# Sheet1.net
KiCad netlist of a schematic drawn in Altium Designer
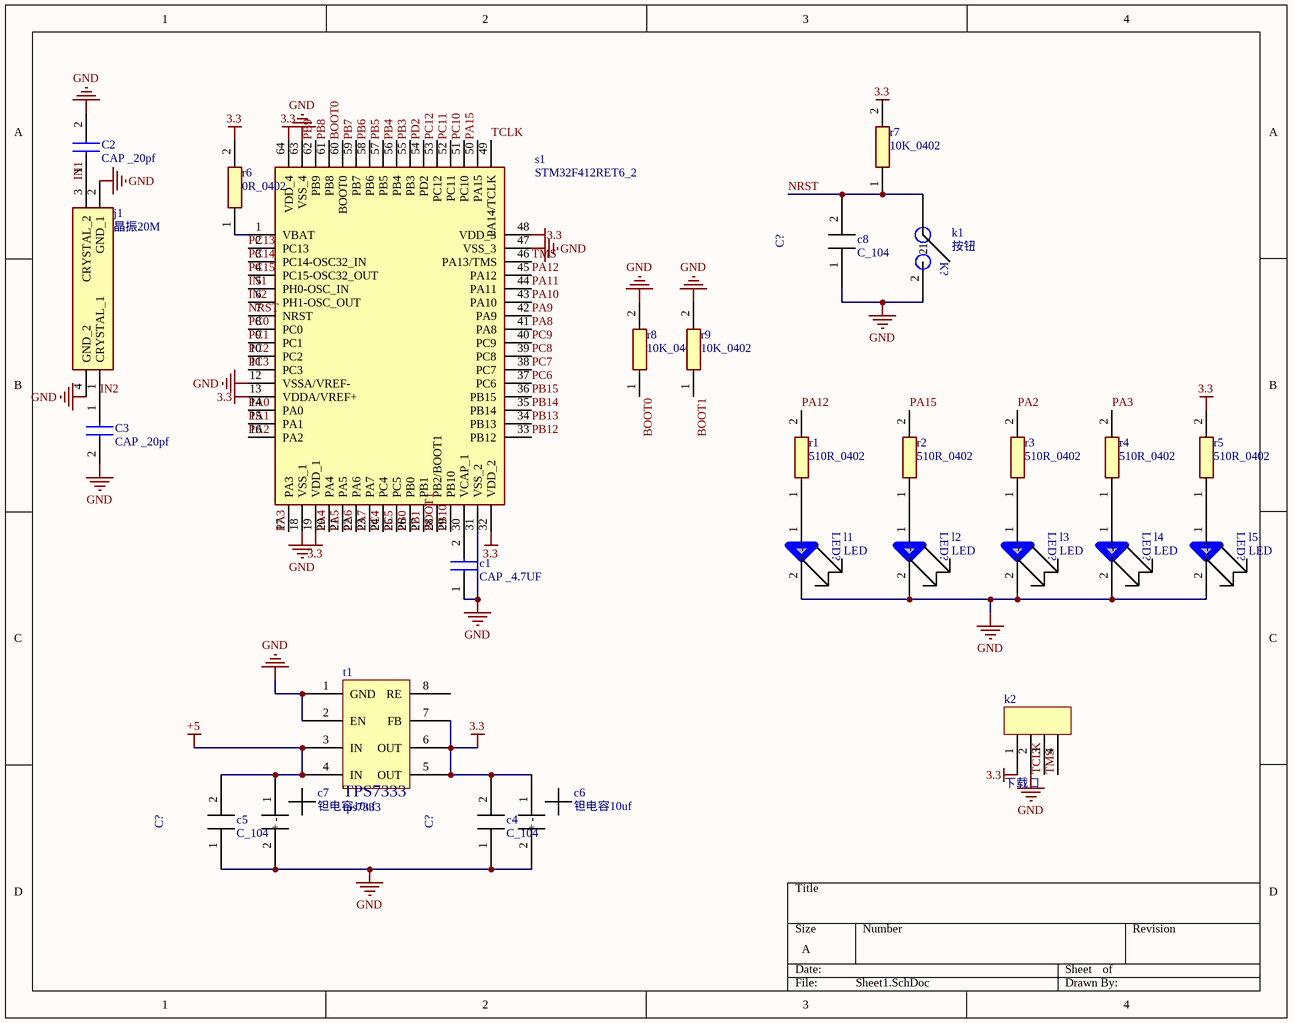
[diagram p0: Sheet1.SchDoc]

(export (version "E")
  (design (tool "Eeschema 10.0.6"))
  (components
    (comp (ref "c1")
      (value "CAP _4.7UF")
      (footprint "cap_0402")
      (libsource (lib "zengjie_Integrated_Library") (part "CAP _20pf"))
    )
    (comp (ref "C2")
      (value "CAP _20pf")
      (footprint "cap_0402")
      (libsource (lib "zengjie_Integrated_Library") (part "CAP _20pf"))
    )
    (comp (ref "C3")
      (value "CAP _20pf")
      (footprint "cap_0402")
      (libsource (lib "zengjie_Integrated_Library") (part "CAP _20pf"))
    )
    (comp (ref "c4")
      (value "C_104")
      (footprint "RC0603")
      (libsource (lib "zengjie_Integrated_Library") (part "C_104"))
    )
    (comp (ref "c5")
      (value "C_104")
      (footprint "RC0603")
      (libsource (lib "zengjie_Integrated_Library") (part "C_104"))
    )
    (comp (ref "c6")
      (value "钽电容10uf")
      (footprint "钽电容10uf 3216")
      (libsource (lib "zengjie_Integrated_Library") (part "钽电容10uf"))
    )
    (comp (ref "c7")
      (value "钽电容10uf")
      (footprint "钽电容10uf 3216")
      (libsource (lib "zengjie_Integrated_Library") (part "钽电容10uf"))
    )
    (comp (ref "c8")
      (value "C_104")
      (footprint "RC0603")
      (libsource (lib "zengjie_Integrated_Library") (part "C_104"))
    )
    (comp (ref "j1")
      (value "晶振20M")
      (footprint "晶振20M")
      (libsource (lib "zengjie_Integrated_Library") (part "晶振20M"))
    )
    (comp (ref "k1")
      (value "按钮")
      (footprint "SMT-KEY")
      (libsource (lib "zengjie_Integrated_Library") (part "按钮"))
    )
    (comp (ref "k2")
      (value "下载口")
      (footprint "贴片4位接口")
      (libsource (lib "zengjie_Integrated_Library") (part "贴片4位"))
    )
    (comp (ref "l1")
      (value "LED")
      (footprint "LED0805")
      (libsource (lib "zengjie_Integrated_Library") (part "LED"))
    )
    (comp (ref "l2")
      (value "LED")
      (footprint "LED0805")
      (libsource (lib "zengjie_Integrated_Library") (part "LED"))
    )
    (comp (ref "l3")
      (value "LED")
      (footprint "LED0805")
      (libsource (lib "zengjie_Integrated_Library") (part "LED"))
    )
    (comp (ref "l4")
      (value "LED")
      (footprint "LED0805")
      (libsource (lib "zengjie_Integrated_Library") (part "LED"))
    )
    (comp (ref "l5")
      (value "LED")
      (footprint "LED0805")
      (libsource (lib "zengjie_Integrated_Library") (part "LED"))
    )
    (comp (ref "r1")
      (value "510R_0402")
      (footprint "RC0402")
      (libsource (lib "zengjie_Integrated_Library") (part "510R_0402"))
    )
    (comp (ref "r2")
      (value "510R_0402")
      (footprint "RC0402")
      (libsource (lib "zengjie_Integrated_Library") (part "510R_0402"))
    )
    (comp (ref "r3")
      (value "510R_0402")
      (footprint "RC0402")
      (libsource (lib "zengjie_Integrated_Library") (part "510R_0402"))
    )
    (comp (ref "r4")
      (value "510R_0402")
      (footprint "RC0402")
      (libsource (lib "zengjie_Integrated_Library") (part "510R_0402"))
    )
    (comp (ref "r5")
      (value "510R_0402")
      (footprint "RC0402")
      (libsource (lib "zengjie_Integrated_Library") (part "510R_0402"))
    )
    (comp (ref "r6")
      (value "0R_0402")
      (footprint "RC0402")
      (libsource (lib "zengjie_Integrated_Library") (part "0R_0402"))
    )
    (comp (ref "r7")
      (value "10K_0402")
      (footprint "RC0402")
      (libsource (lib "zengjie_Integrated_Library") (part "10K_0402"))
    )
    (comp (ref "r8")
      (value "10K_0402")
      (footprint "RC0402")
      (libsource (lib "zengjie_Integrated_Library") (part "10K_0402"))
    )
    (comp (ref "r9")
      (value "10K_0402")
      (footprint "RC0402")
      (libsource (lib "zengjie_Integrated_Library") (part "10K_0402"))
    )
    (comp (ref "s1")
      (value "STM32F412RET6_2")
      (footprint "stm32f412ret6 _2")
      (libsource (lib "zengjie_Integrated_Library") (part "STM32F412RET6_2"))
    )
    (comp (ref "t1")
      (value "tps7333")
      (footprint "SOIC-8P")
      (libsource (lib "zengjie_Integrated_Library") (part "tps7333"))
    )
  )
  (nets
    (net (code "1") (name "+5") (class "Default")
      (node (ref "c5") (pin "2") (pinfunction "2_2") (pintype "passive"))
      (node (ref "c7") (pin "1") (pinfunction "+_1") (pintype "passive"))
      (node (ref "t1") (pin "3") (pinfunction "IN_3") (pintype "passive"))
      (node (ref "t1") (pin "4") (pinfunction "IN_4") (pintype "passive"))
    )
    (net (code "2") (name "/BOOT0") (class "Default")
      (node (ref "r8") (pin "1") (pinfunction "1_1") (pintype "passive"))
      (node (ref "s1") (pin "60") (pinfunction "BOOT0_60") (pintype "passive"))
    )
    (net (code "3") (name "/BOOT1") (class "Default")
      (node (ref "r9") (pin "1") (pinfunction "1_1") (pintype "passive"))
      (node (ref "s1") (pin "28") (pinfunction "PB2/BOOT1_28") (pintype "passive"))
    )
    (net (code "4") (name "/IN1") (class "Default")
      (node (ref "C2") (pin "1") (pinfunction "1_1") (pintype "passive"))
      (node (ref "j1") (pin "3") (pinfunction "CRYSTAL_2_3") (pintype "passive"))
      (node (ref "s1") (pin "5") (pinfunction "PH0-OSC_IN_5") (pintype "passive"))
    )
    (net (code "5") (name "/IN2") (class "Default")
      (node (ref "C3") (pin "1") (pinfunction "1_1") (pintype "passive"))
      (node (ref "j1") (pin "1") (pinfunction "CRYSTAL_1_1") (pintype "passive"))
      (node (ref "s1") (pin "6") (pinfunction "PH1-OSC_OUT_6") (pintype "passive"))
    )
    (net (code "6") (name "/NRST") (class "Default")
      (node (ref "c8") (pin "2") (pinfunction "2_2") (pintype "passive"))
      (node (ref "k1") (pin "1") (pinfunction "1_1") (pintype "passive"))
      (node (ref "r7") (pin "1") (pinfunction "1_1") (pintype "passive"))
      (node (ref "s1") (pin "7") (pinfunction "NRST_7") (pintype "passive"))
    )
    (net (code "7") (name "/PA0") (class "Default")
      (node (ref "s1") (pin "14") (pinfunction "PA0_14") (pintype "passive"))
    )
    (net (code "8") (name "/PA1") (class "Default")
      (node (ref "s1") (pin "15") (pinfunction "PA1_15") (pintype "passive"))
    )
    (net (code "9") (name "/PA2") (class "Default")
      (node (ref "r3") (pin "2") (pinfunction "2_2") (pintype "passive"))
      (node (ref "s1") (pin "16") (pinfunction "PA2_16") (pintype "passive"))
    )
    (net (code "10") (name "/PA3") (class "Default")
      (node (ref "r4") (pin "2") (pinfunction "2_2") (pintype "passive"))
      (node (ref "s1") (pin "17") (pinfunction "PA3_17") (pintype "passive"))
    )
    (net (code "11") (name "/PA4") (class "Default")
      (node (ref "s1") (pin "20") (pinfunction "PA4_20") (pintype "passive"))
    )
    (net (code "12") (name "/PA5") (class "Default")
      (node (ref "s1") (pin "21") (pinfunction "PA5_21") (pintype "passive"))
    )
    (net (code "13") (name "/PA6") (class "Default")
      (node (ref "s1") (pin "22") (pinfunction "PA6_22") (pintype "passive"))
    )
    (net (code "14") (name "/PA7") (class "Default")
      (node (ref "s1") (pin "23") (pinfunction "PA7_23") (pintype "passive"))
    )
    (net (code "15") (name "/PA8") (class "Default")
      (node (ref "s1") (pin "41") (pinfunction "PA8_41") (pintype "passive"))
    )
    (net (code "16") (name "/PA9") (class "Default")
      (node (ref "s1") (pin "42") (pinfunction "PA9_42") (pintype "passive"))
    )
    (net (code "17") (name "/PA10") (class "Default")
      (node (ref "s1") (pin "43") (pinfunction "PA10_43") (pintype "passive"))
    )
    (net (code "18") (name "/PA11") (class "Default")
      (node (ref "s1") (pin "44") (pinfunction "PA11_44") (pintype "passive"))
    )
    (net (code "19") (name "/PA12") (class "Default")
      (node (ref "r1") (pin "2") (pinfunction "2_2") (pintype "passive"))
      (node (ref "s1") (pin "45") (pinfunction "PA12_45") (pintype "passive"))
    )
    (net (code "20") (name "/PA15") (class "Default")
      (node (ref "r2") (pin "2") (pinfunction "2_2") (pintype "passive"))
      (node (ref "s1") (pin "50") (pinfunction "PA15_50") (pintype "passive"))
    )
    (net (code "21") (name "/PB0") (class "Default")
      (node (ref "s1") (pin "26") (pinfunction "PB0_26") (pintype "passive"))
    )
    (net (code "22") (name "/PB1") (class "Default")
      (node (ref "s1") (pin "27") (pinfunction "PB1_27") (pintype "passive"))
    )
    (net (code "23") (name "/PB3") (class "Default")
      (node (ref "s1") (pin "55") (pinfunction "PB3_55") (pintype "passive"))
    )
    (net (code "24") (name "/PB4") (class "Default")
      (node (ref "s1") (pin "56") (pinfunction "PB4_56") (pintype "passive"))
    )
    (net (code "25") (name "/PB5") (class "Default")
      (node (ref "s1") (pin "57") (pinfunction "PB5_57") (pintype "passive"))
    )
    (net (code "26") (name "/PB6") (class "Default")
      (node (ref "s1") (pin "58") (pinfunction "PB6_58") (pintype "passive"))
    )
    (net (code "27") (name "/PB7") (class "Default")
      (node (ref "s1") (pin "59") (pinfunction "PB7_59") (pintype "passive"))
    )
    (net (code "28") (name "/PB8") (class "Default")
      (node (ref "s1") (pin "61") (pinfunction "PB8_61") (pintype "passive"))
    )
    (net (code "29") (name "/PB9") (class "Default")
      (node (ref "s1") (pin "62") (pinfunction "PB9_62") (pintype "passive"))
    )
    (net (code "30") (name "/PB10") (class "Default")
      (node (ref "s1") (pin "29") (pinfunction "PB10_29") (pintype "passive"))
    )
    (net (code "31") (name "/PB12") (class "Default")
      (node (ref "s1") (pin "33") (pinfunction "PB12_33") (pintype "passive"))
    )
    (net (code "32") (name "/PB13") (class "Default")
      (node (ref "s1") (pin "34") (pinfunction "PB13_34") (pintype "passive"))
    )
    (net (code "33") (name "/PB14") (class "Default")
      (node (ref "s1") (pin "35") (pinfunction "PB14_35") (pintype "passive"))
    )
    (net (code "34") (name "/PB15") (class "Default")
      (node (ref "s1") (pin "36") (pinfunction "PB15_36") (pintype "passive"))
    )
    (net (code "35") (name "/PC0") (class "Default")
      (node (ref "s1") (pin "8") (pinfunction "PC0_8") (pintype "passive"))
    )
    (net (code "36") (name "/PC1") (class "Default")
      (node (ref "s1") (pin "9") (pinfunction "PC1_9") (pintype "passive"))
    )
    (net (code "37") (name "/PC2") (class "Default")
      (node (ref "s1") (pin "10") (pinfunction "PC2_10") (pintype "passive"))
    )
    (net (code "38") (name "/PC3") (class "Default")
      (node (ref "s1") (pin "11") (pinfunction "PC3_11") (pintype "passive"))
    )
    (net (code "39") (name "/PC4") (class "Default")
      (node (ref "s1") (pin "24") (pinfunction "PC4_24") (pintype "passive"))
    )
    (net (code "40") (name "/PC5") (class "Default")
      (node (ref "s1") (pin "25") (pinfunction "PC5_25") (pintype "passive"))
    )
    (net (code "41") (name "/PC6") (class "Default")
      (node (ref "s1") (pin "37") (pinfunction "PC6_37") (pintype "passive"))
    )
    (net (code "42") (name "/PC7") (class "Default")
      (node (ref "s1") (pin "38") (pinfunction "PC7_38") (pintype "passive"))
    )
    (net (code "43") (name "/PC8") (class "Default")
      (node (ref "s1") (pin "39") (pinfunction "PC8_39") (pintype "passive"))
    )
    (net (code "44") (name "/PC9") (class "Default")
      (node (ref "s1") (pin "40") (pinfunction "PC9_40") (pintype "passive"))
    )
    (net (code "45") (name "/PC10") (class "Default")
      (node (ref "s1") (pin "51") (pinfunction "PC10_51") (pintype "passive"))
    )
    (net (code "46") (name "/PC11") (class "Default")
      (node (ref "s1") (pin "52") (pinfunction "PC11_52") (pintype "passive"))
    )
    (net (code "47") (name "/PC12") (class "Default")
      (node (ref "s1") (pin "53") (pinfunction "PC12_53") (pintype "passive"))
    )
    (net (code "48") (name "/PC13") (class "Default")
      (node (ref "s1") (pin "2") (pinfunction "PC13_2") (pintype "passive"))
    )
    (net (code "49") (name "/PC14") (class "Default")
      (node (ref "s1") (pin "3") (pinfunction "PC14-OSC32_IN_3") (pintype "passive"))
    )
    (net (code "50") (name "/PC15") (class "Default")
      (node (ref "s1") (pin "4") (pinfunction "PC15-OSC32_OUT_4") (pintype "passive"))
    )
    (net (code "51") (name "/PD2") (class "Default")
      (node (ref "s1") (pin "54") (pinfunction "PD2_54") (pintype "passive"))
    )
    (net (code "52") (name "/TCLK") (class "Default")
      (node (ref "k2") (pin "3") (pintype "passive"))
      (node (ref "s1") (pin "49") (pinfunction "PA14/TCLK_49") (pintype "passive"))
    )
    (net (code "53") (name "/TMS") (class "Default")
      (node (ref "k2") (pin "4") (pintype "passive"))
      (node (ref "s1") (pin "46") (pinfunction "PA13/TMS_46") (pintype "passive"))
    )
    (net (code "54") (name "3.3") (class "Default")
      (node (ref "c4") (pin "2") (pinfunction "2_2") (pintype "passive"))
      (node (ref "c6") (pin "1") (pinfunction "+_1") (pintype "passive"))
      (node (ref "k2") (pin "1") (pintype "passive"))
      (node (ref "r5") (pin "2") (pinfunction "2_2") (pintype "passive"))
      (node (ref "r6") (pin "2") (pinfunction "2_2") (pintype "passive"))
      (node (ref "s1") (pin "13") (pinfunction "VDDA/VREF+_13") (pintype "passive"))
      (node (ref "s1") (pin "19") (pinfunction "VDD_1_19") (pintype "passive"))
      (node (ref "s1") (pin "32") (pinfunction "VDD_2_32") (pintype "passive"))
      (node (ref "s1") (pin "48") (pinfunction "VDD_3_48") (pintype "passive"))
      (node (ref "s1") (pin "64") (pinfunction "VDD_4_64") (pintype "passive"))
      (node (ref "t1") (pin "5") (pinfunction "OUT_5") (pintype "passive"))
      (node (ref "t1") (pin "6") (pinfunction "OUT_6") (pintype "passive"))
      (node (ref "t1") (pin "7") (pinfunction "FB_7") (pintype "passive"))
    )
    (net (code "55") (name "GND") (class "Default")
      (node (ref "C2") (pin "2") (pinfunction "2_2") (pintype "passive"))
      (node (ref "C3") (pin "2") (pinfunction "2_2") (pintype "passive"))
      (node (ref "c1") (pin "1") (pinfunction "1_1") (pintype "passive"))
      (node (ref "c4") (pin "1") (pinfunction "1_1") (pintype "passive"))
      (node (ref "c5") (pin "1") (pinfunction "1_1") (pintype "passive"))
      (node (ref "c6") (pin "2") (pinfunction "-_2") (pintype "passive"))
      (node (ref "c7") (pin "2") (pinfunction "-_2") (pintype "passive"))
      (node (ref "c8") (pin "1") (pinfunction "1_1") (pintype "passive"))
      (node (ref "j1") (pin "2") (pinfunction "GND_1_2") (pintype "passive"))
      (node (ref "j1") (pin "4") (pinfunction "GND_2_4") (pintype "passive"))
      (node (ref "k1") (pin "2") (pinfunction "2_2") (pintype "passive"))
      (node (ref "k2") (pin "2") (pintype "passive"))
      (node (ref "l1") (pin "2") (pinfunction "-_2") (pintype "passive"))
      (node (ref "l2") (pin "2") (pinfunction "-_2") (pintype "passive"))
      (node (ref "l3") (pin "2") (pinfunction "-_2") (pintype "passive"))
      (node (ref "l4") (pin "2") (pinfunction "-_2") (pintype "passive"))
      (node (ref "l5") (pin "2") (pinfunction "-_2") (pintype "passive"))
      (node (ref "r8") (pin "2") (pinfunction "2_2") (pintype "passive"))
      (node (ref "r9") (pin "2") (pinfunction "2_2") (pintype "passive"))
      (node (ref "s1") (pin "12") (pinfunction "VSSA/VREF-_12") (pintype "passive"))
      (node (ref "s1") (pin "18") (pinfunction "VSS_1_18") (pintype "passive"))
      (node (ref "s1") (pin "31") (pinfunction "VSS_2_31") (pintype "passive"))
      (node (ref "s1") (pin "47") (pinfunction "VSS_3_47") (pintype "passive"))
      (node (ref "s1") (pin "63") (pinfunction "VSS_4_63") (pintype "passive"))
      (node (ref "t1") (pin "1") (pinfunction "GND_1") (pintype "passive"))
      (node (ref "t1") (pin "2") (pinfunction "EN_2") (pintype "passive"))
    )
    (net (code "56") (name "Net-(l1-+)") (class "Default")
      (node (ref "l1") (pin "1") (pinfunction "+_1") (pintype "passive"))
      (node (ref "r1") (pin "1") (pinfunction "1_1") (pintype "passive"))
    )
    (net (code "57") (name "Net-(l2-+)") (class "Default")
      (node (ref "l2") (pin "1") (pinfunction "+_1") (pintype "passive"))
      (node (ref "r2") (pin "1") (pinfunction "1_1") (pintype "passive"))
    )
    (net (code "58") (name "Net-(l3-+)") (class "Default")
      (node (ref "l3") (pin "1") (pinfunction "+_1") (pintype "passive"))
      (node (ref "r3") (pin "1") (pinfunction "1_1") (pintype "passive"))
    )
    (net (code "59") (name "Net-(l4-+)") (class "Default")
      (node (ref "l4") (pin "1") (pinfunction "+_1") (pintype "passive"))
      (node (ref "r4") (pin "1") (pinfunction "1_1") (pintype "passive"))
    )
    (net (code "60") (name "Net-(l5-+)") (class "Default")
      (node (ref "l5") (pin "1") (pinfunction "+_1") (pintype "passive"))
      (node (ref "r5") (pin "1") (pinfunction "1_1") (pintype "passive"))
    )
    (net (code "61") (name "Net-(s1-VBAT)") (class "Default")
      (node (ref "r6") (pin "1") (pinfunction "1_1") (pintype "passive"))
      (node (ref "s1") (pin "1") (pinfunction "VBAT_1") (pintype "passive"))
    )
    (net (code "62") (name "Net-(s1-VCAP_1)") (class "Default")
      (node (ref "c1") (pin "2") (pinfunction "2_2") (pintype "passive"))
      (node (ref "s1") (pin "30") (pinfunction "VCAP_1_30") (pintype "passive"))
    )
    (net (code "63") (name "unconnected-(r7-Pad2)") (class "Default")
      (node (ref "r7") (pin "2") (pinfunction "2_2") (pintype "passive"))
    )
    (net (code "64") (name "unconnected-(t1-RE-Pad8)") (class "Default")
      (node (ref "t1") (pin "8") (pinfunction "RE_8") (pintype "passive"))
    )
  )
)
